# STlink_V3E_PWR.net
KiCad netlist of a schematic drawn in Altium Designer
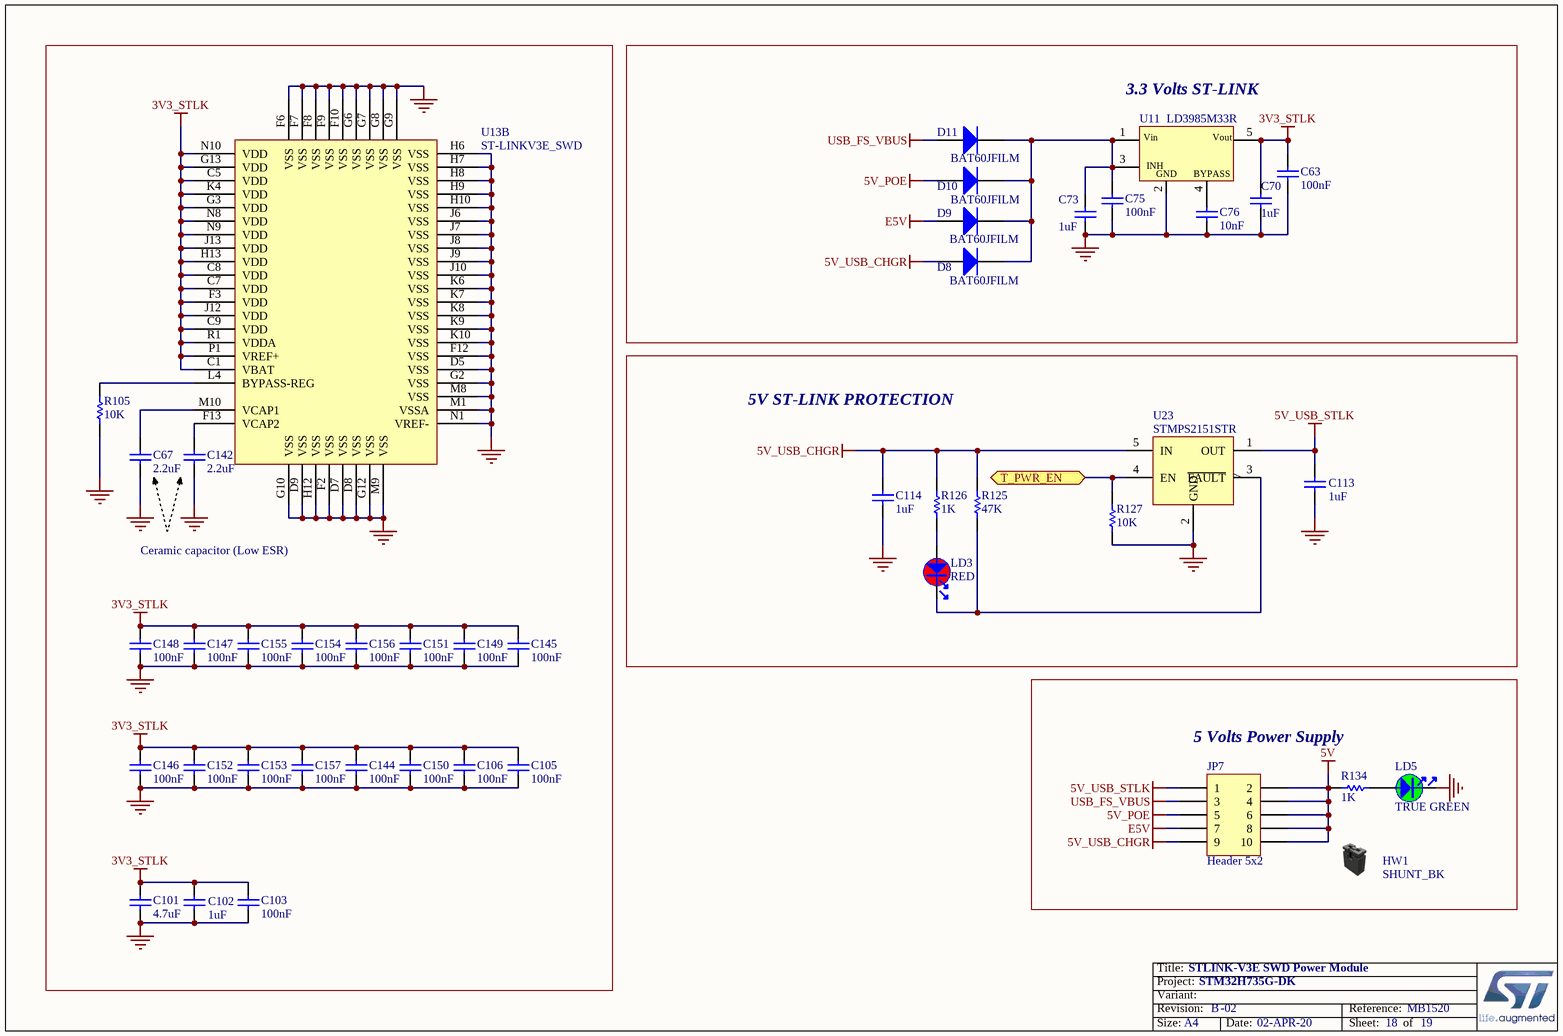
[diagram p0: STlink_V3E_PWR.SchDoc]

(export (version "E")
  (design (tool "Eeschema 10.0.6"))
  (components
    (comp (ref "C63")
      (value "100nF")
      (footprint "C0402")
      (description "Capacitor, MLCC, 100nF, 16V, X7R, 10%, 0402, T=0,5mm")
      (fields
        (field (name "INTERNAL_PART_NUMBER") "MCD-00102")
        (field (name "MANUFACTURER_PART_NUMBER") "CC0402KRX7R7BB104")
        (field (name "PROVIDED_BY") "SUBCO")
      )
      (libsource (lib "MCD_PARTS_database") (part "Capacitor"))
    )
    (comp (ref "C67")
      (value "2.2uF")
      (footprint "C1206_H1P15")
      (description "Capacitor, MLCC, 2.2uF, 16V, X7R, 10%, 1206, T=1,15mm")
      (fields
        (field (name "INTERNAL_PART_NUMBER") "MCD-00008")
        (field (name "MANUFACTURER_PART_NUMBER") "CC1206KKX7R7BB225")
        (field (name "PROVIDED_BY") "SUBCO")
      )
      (libsource (lib "MCD_PARTS_database") (part "Capacitor"))
    )
    (comp (ref "C70")
      (value "1uF")
      (footprint "C0603")
      (description "Capacitor, MLCC, 1uF, 16V, X5R, 10%, 0603, T=0,8mm")
      (fields
        (field (name "INTERNAL_PART_NUMBER") "MCD-00010")
        (field (name "MANUFACTURER_PART_NUMBER") "CC0603KRX5R7BB105")
        (field (name "PROVIDED_BY") "SUBCO")
      )
      (libsource (lib "MCD_PARTS_database") (part "Capacitor"))
    )
    (comp (ref "C73")
      (value "1uF")
      (footprint "C0603")
      (description "Capacitor, MLCC, 1uF, 6V3, X5R, 10%, 0603, T=0,8mm")
      (fields
        (field (name "INTERNAL_PART_NUMBER") "MCD-00238")
        (field (name "MANUFACTURER_PART_NUMBER") "CC0603KRX5R5BB105")
        (field (name "PROVIDED_BY") "SUBCO")
      )
      (libsource (lib "MCD_PARTS_database") (part "Capacitor"))
    )
    (comp (ref "C75")
      (value "100nF")
      (footprint "C0402")
      (description "Capacitor, MLCC, 100nF, 16V, X7R, 10%, 0402, T=0,5mm")
      (fields
        (field (name "INTERNAL_PART_NUMBER") "MCD-00102")
        (field (name "MANUFACTURER_PART_NUMBER") "CC0402KRX7R7BB104")
        (field (name "PROVIDED_BY") "SUBCO")
      )
      (libsource (lib "MCD_PARTS_database") (part "Capacitor"))
    )
    (comp (ref "C76")
      (value "10nF")
      (footprint "C0402")
      (description "Capacitor, MLCC, 10nF, 16V, X7R, 10%, 0402, T=0.5mm")
      (fields
        (field (name "INTERNAL_PART_NUMBER") "MCD-00011")
        (field (name "MANUFACTURER_PART_NUMBER") "CC0402KRX7R7BB103")
        (field (name "PROVIDED_BY") "SUBCO")
      )
      (libsource (lib "MCD_PARTS_database") (part "Capacitor"))
    )
    (comp (ref "C101")
      (value "4.7uF")
      (footprint "C0603")
      (description "Capacitor, MLCC, 4.7uF, 16V, X5R, 10%, 0603, T=0.8mm")
      (fields
        (field (name "INTERNAL_PART_NUMBER") "MCD-00009")
        (field (name "MANUFACTURER_PART_NUMBER") "CC0603KRX5R7BB475")
        (field (name "PROVIDED_BY") "SUBCO")
      )
      (libsource (lib "MCD_PARTS_database") (part "Capacitor"))
    )
    (comp (ref "C102")
      (value "1uF")
      (footprint "C0603")
      (description "Capacitor, MLCC, 1uF, 16V, X5R, 10%, 0603, T=0,8mm")
      (fields
        (field (name "INTERNAL_PART_NUMBER") "MCD-00010")
        (field (name "MANUFACTURER_PART_NUMBER") "CC0603KRX5R7BB105")
        (field (name "PROVIDED_BY") "SUBCO")
      )
      (libsource (lib "MCD_PARTS_database") (part "Capacitor"))
    )
    (comp (ref "C103")
      (value "100nF")
      (footprint "C0402")
      (description "Capacitor, MLCC, 100nF, 16V, X7R, 10%, 0402, T=0,5mm")
      (fields
        (field (name "INTERNAL_PART_NUMBER") "MCD-00102")
        (field (name "MANUFACTURER_PART_NUMBER") "CC0402KRX7R7BB104")
        (field (name "PROVIDED_BY") "SUBCO")
      )
      (libsource (lib "MCD_PARTS_database") (part "Capacitor"))
    )
    (comp (ref "C105")
      (value "100nF")
      (footprint "C0402")
      (description "Capacitor, MLCC, 100nF, 16V, X7R, 10%, 0402, T=0,5mm")
      (fields
        (field (name "INTERNAL_PART_NUMBER") "MCD-00102")
        (field (name "MANUFACTURER_PART_NUMBER") "CC0402KRX7R7BB104")
        (field (name "PROVIDED_BY") "SUBCO")
      )
      (libsource (lib "MCD_PARTS_database") (part "Capacitor"))
    )
    (comp (ref "C106")
      (value "100nF")
      (footprint "C0402")
      (description "Capacitor, MLCC, 100nF, 16V, X7R, 10%, 0402, T=0,5mm")
      (fields
        (field (name "INTERNAL_PART_NUMBER") "MCD-00102")
        (field (name "MANUFACTURER_PART_NUMBER") "CC0402KRX7R7BB104")
        (field (name "PROVIDED_BY") "SUBCO")
      )
      (libsource (lib "MCD_PARTS_database") (part "Capacitor"))
    )
    (comp (ref "C113")
      (value "1uF")
      (footprint "C0603")
      (description "Capacitor, MLCC, 1uF, 16V, X5R, 10%, 0603, T=0,8mm")
      (fields
        (field (name "INTERNAL_PART_NUMBER") "MCD-00010")
        (field (name "MANUFACTURER_PART_NUMBER") "CC0603KRX5R7BB105")
        (field (name "PROVIDED_BY") "SUBCO")
      )
      (libsource (lib "MCD_PARTS_database") (part "Capacitor"))
    )
    (comp (ref "C114")
      (value "1uF")
      (footprint "C0603")
      (description "Capacitor, MLCC, 1uF, 16V, X5R, 10%, 0603, T=0,8mm")
      (fields
        (field (name "INTERNAL_PART_NUMBER") "MCD-00010")
        (field (name "MANUFACTURER_PART_NUMBER") "CC0603KRX5R7BB105")
        (field (name "PROVIDED_BY") "SUBCO")
      )
      (libsource (lib "MCD_PARTS_database") (part "Capacitor"))
    )
    (comp (ref "C142")
      (value "2.2uF")
      (footprint "C1206_H1P15")
      (description "Capacitor, MLCC, 2.2uF, 16V, X7R, 10%, 1206, T=1,15mm")
      (fields
        (field (name "INTERNAL_PART_NUMBER") "MCD-00008")
        (field (name "MANUFACTURER_PART_NUMBER") "CC1206KKX7R7BB225")
        (field (name "PROVIDED_BY") "SUBCO")
      )
      (libsource (lib "MCD_PARTS_database") (part "Capacitor"))
    )
    (comp (ref "C144")
      (value "100nF")
      (footprint "C0402")
      (description "Capacitor, MLCC, 100nF, 16V, X7R, 10%, 0402, T=0,5mm")
      (fields
        (field (name "INTERNAL_PART_NUMBER") "MCD-00102")
        (field (name "MANUFACTURER_PART_NUMBER") "CC0402KRX7R7BB104")
        (field (name "PROVIDED_BY") "SUBCO")
      )
      (libsource (lib "MCD_PARTS_database") (part "Capacitor"))
    )
    (comp (ref "C145")
      (value "100nF")
      (footprint "C0402")
      (description "Capacitor, MLCC, 100nF, 16V, X7R, 10%, 0402, T=0,5mm")
      (fields
        (field (name "INTERNAL_PART_NUMBER") "MCD-00102")
        (field (name "MANUFACTURER_PART_NUMBER") "CC0402KRX7R7BB104")
        (field (name "PROVIDED_BY") "SUBCO")
      )
      (libsource (lib "MCD_PARTS_database") (part "Capacitor"))
    )
    (comp (ref "C146")
      (value "100nF")
      (footprint "C0402")
      (description "Capacitor, MLCC, 100nF, 16V, X7R, 10%, 0402, T=0,5mm")
      (fields
        (field (name "INTERNAL_PART_NUMBER") "MCD-00102")
        (field (name "MANUFACTURER_PART_NUMBER") "CC0402KRX7R7BB104")
        (field (name "PROVIDED_BY") "SUBCO")
      )
      (libsource (lib "MCD_PARTS_database") (part "Capacitor"))
    )
    (comp (ref "C147")
      (value "100nF")
      (footprint "C0402")
      (description "Capacitor, MLCC, 100nF, 16V, X7R, 10%, 0402, T=0,5mm")
      (fields
        (field (name "INTERNAL_PART_NUMBER") "MCD-00102")
        (field (name "MANUFACTURER_PART_NUMBER") "CC0402KRX7R7BB104")
        (field (name "PROVIDED_BY") "SUBCO")
      )
      (libsource (lib "MCD_PARTS_database") (part "Capacitor"))
    )
    (comp (ref "C148")
      (value "100nF")
      (footprint "C0402")
      (description "Capacitor, MLCC, 100nF, 16V, X7R, 10%, 0402, T=0,5mm")
      (fields
        (field (name "INTERNAL_PART_NUMBER") "MCD-00102")
        (field (name "MANUFACTURER_PART_NUMBER") "CC0402KRX7R7BB104")
        (field (name "PROVIDED_BY") "SUBCO")
      )
      (libsource (lib "MCD_PARTS_database") (part "Capacitor"))
    )
    (comp (ref "C149")
      (value "100nF")
      (footprint "C0402")
      (description "Capacitor, MLCC, 100nF, 16V, X7R, 10%, 0402, T=0,5mm")
      (fields
        (field (name "INTERNAL_PART_NUMBER") "MCD-00102")
        (field (name "MANUFACTURER_PART_NUMBER") "CC0402KRX7R7BB104")
        (field (name "PROVIDED_BY") "SUBCO")
      )
      (libsource (lib "MCD_PARTS_database") (part "Capacitor"))
    )
    (comp (ref "C150")
      (value "100nF")
      (footprint "C0402")
      (description "Capacitor, MLCC, 100nF, 16V, X7R, 10%, 0402, T=0,5mm")
      (fields
        (field (name "INTERNAL_PART_NUMBER") "MCD-00102")
        (field (name "MANUFACTURER_PART_NUMBER") "CC0402KRX7R7BB104")
        (field (name "PROVIDED_BY") "SUBCO")
      )
      (libsource (lib "MCD_PARTS_database") (part "Capacitor"))
    )
    (comp (ref "C151")
      (value "100nF")
      (footprint "C0402")
      (description "Capacitor, MLCC, 100nF, 16V, X7R, 10%, 0402, T=0,5mm")
      (fields
        (field (name "INTERNAL_PART_NUMBER") "MCD-00102")
        (field (name "MANUFACTURER_PART_NUMBER") "CC0402KRX7R7BB104")
        (field (name "PROVIDED_BY") "SUBCO")
      )
      (libsource (lib "MCD_PARTS_database") (part "Capacitor"))
    )
    (comp (ref "C152")
      (value "100nF")
      (footprint "C0402")
      (description "Capacitor, MLCC, 100nF, 16V, X7R, 10%, 0402, T=0,5mm")
      (fields
        (field (name "INTERNAL_PART_NUMBER") "MCD-00102")
        (field (name "MANUFACTURER_PART_NUMBER") "CC0402KRX7R7BB104")
        (field (name "PROVIDED_BY") "SUBCO")
      )
      (libsource (lib "MCD_PARTS_database") (part "Capacitor"))
    )
    (comp (ref "C153")
      (value "100nF")
      (footprint "C0402")
      (description "Capacitor, MLCC, 100nF, 16V, X7R, 10%, 0402, T=0,5mm")
      (fields
        (field (name "INTERNAL_PART_NUMBER") "MCD-00102")
        (field (name "MANUFACTURER_PART_NUMBER") "CC0402KRX7R7BB104")
        (field (name "PROVIDED_BY") "SUBCO")
      )
      (libsource (lib "MCD_PARTS_database") (part "Capacitor"))
    )
    (comp (ref "C154")
      (value "100nF")
      (footprint "C0402")
      (description "Capacitor, MLCC, 100nF, 16V, X7R, 10%, 0402, T=0,5mm")
      (fields
        (field (name "INTERNAL_PART_NUMBER") "MCD-00102")
        (field (name "MANUFACTURER_PART_NUMBER") "CC0402KRX7R7BB104")
        (field (name "PROVIDED_BY") "SUBCO")
      )
      (libsource (lib "MCD_PARTS_database") (part "Capacitor"))
    )
    (comp (ref "C155")
      (value "100nF")
      (footprint "C0402")
      (description "Capacitor, MLCC, 100nF, 16V, X7R, 10%, 0402, T=0,5mm")
      (fields
        (field (name "INTERNAL_PART_NUMBER") "MCD-00102")
        (field (name "MANUFACTURER_PART_NUMBER") "CC0402KRX7R7BB104")
        (field (name "PROVIDED_BY") "SUBCO")
      )
      (libsource (lib "MCD_PARTS_database") (part "Capacitor"))
    )
    (comp (ref "C156")
      (value "100nF")
      (footprint "C0402")
      (description "Capacitor, MLCC, 100nF, 16V, X7R, 10%, 0402, T=0,5mm")
      (fields
        (field (name "INTERNAL_PART_NUMBER") "MCD-00102")
        (field (name "MANUFACTURER_PART_NUMBER") "CC0402KRX7R7BB104")
        (field (name "PROVIDED_BY") "SUBCO")
      )
      (libsource (lib "MCD_PARTS_database") (part "Capacitor"))
    )
    (comp (ref "C157")
      (value "100nF")
      (footprint "C0402")
      (description "Capacitor, MLCC, 100nF, 16V, X7R, 10%, 0402, T=0,5mm")
      (fields
        (field (name "INTERNAL_PART_NUMBER") "MCD-00102")
        (field (name "MANUFACTURER_PART_NUMBER") "CC0402KRX7R7BB104")
        (field (name "PROVIDED_BY") "SUBCO")
      )
      (libsource (lib "MCD_PARTS_database") (part "Capacitor"))
    )
    (comp (ref "D8")
      (value "BAT60JFILM")
      (footprint "DIO_SOD323")
      (fields
        (field (name "INTERNAL_PART_NUMBER") "MCD-00034")
        (field (name "MANUFACTURER") "STMICROELECTRONICS")
        (field (name "BMS_PART_NUMBER") "9151097")
        (field (name "PROVIDED_BY") "SUBCO with ST control")
      )
      (libsource (lib "MCD_PARTS_database") (part "BAT60JFILM"))
    )
    (comp (ref "D9")
      (value "BAT60JFILM")
      (footprint "DIO_SOD323")
      (fields
        (field (name "INTERNAL_PART_NUMBER") "MCD-00034")
        (field (name "MANUFACTURER") "STMICROELECTRONICS")
        (field (name "BMS_PART_NUMBER") "9151097")
        (field (name "PROVIDED_BY") "SUBCO with ST control")
      )
      (libsource (lib "MCD_PARTS_database") (part "BAT60JFILM"))
    )
    (comp (ref "D10")
      (value "BAT60JFILM")
      (footprint "DIO_SOD323")
      (fields
        (field (name "INTERNAL_PART_NUMBER") "MCD-00034")
        (field (name "MANUFACTURER") "STMICROELECTRONICS")
        (field (name "BMS_PART_NUMBER") "9151097")
        (field (name "PROVIDED_BY") "SUBCO with ST control")
      )
      (libsource (lib "MCD_PARTS_database") (part "BAT60JFILM"))
    )
    (comp (ref "D11")
      (value "BAT60JFILM")
      (footprint "DIO_SOD323")
      (fields
        (field (name "INTERNAL_PART_NUMBER") "MCD-00034")
        (field (name "MANUFACTURER") "STMICROELECTRONICS")
        (field (name "BMS_PART_NUMBER") "9151097")
        (field (name "PROVIDED_BY") "SUBCO with ST control")
      )
      (libsource (lib "MCD_PARTS_database") (part "BAT60JFILM"))
    )
    (comp (ref "HW1")
      (value "SHUNT_BK")
      (footprint "NA")
      (description "SHUNT, 2.54mm, height 6.10mm, BLACK")
      (fields
        (field (name "INTERNAL_PART_NUMBER") "MCD-00122")
        (field (name "MANUFACTURER_PART_NUMBER") "SNT-100-BK-G")
        (field (name "PROVIDED_BY") "SUBCO")
      )
      (libsource (lib "MCD_PARTS_database") (part "Shunt Black 2.54mm"))
    )
    (comp (ref "JP7")
      (value "Header 5x2")
      (footprint "CON_988-JIUBABA_PHFS25-12-10-G0B115-T-1")
      (description "Header, 5x2, 2.54mm, VR, TH, Height 6mm/3mm")
      (fields
        (field (name "INTERNAL_PART_NUMBER") "MCD-00312")
        (field (name "MANUFACTURER_PART_NUMBER") "PHFS25-12-10-G0B115-T-1")
        (field (name "PROVIDED_BY") "SUBCO")
      )
      (libsource (lib "MCD_PARTS_database") (part "Header 5x2"))
    )
    (comp (ref "LD3")
      (value "RED")
      (footprint "LED_0603_VISHAY_VLMS1300-GS08_RED_1A2K_H0P8")
      (description "LED Red, 0603 SMD, 2V Forward Voltage")
      (fields
        (field (name "INTERNAL_PART_NUMBER") "MCD-00587")
        (field (name "MANUFACTURER_PART_NUMBER") "VLMS1300-GS08")
        (field (name "PROVIDED_BY") "SUBCO")
      )
      (libsource (lib "MCD_PARTS_database") (part "LED_red"))
    )
    (comp (ref "LD5")
      (value "TRUE GREEN")
      (footprint "LED_0603_VISHAY_VLMTG1300-GS08_GREEN_1A2K_H0P8")
      (description "LED Green, 0603 SMD, Fw Voltage = 2.8V - 3.6V")
      (fields
        (field (name "INTERNAL_PART_NUMBER") "MCD-00589")
        (field (name "MANUFACTURER_PART_NUMBER") "VLMTG1300-GS08")
        (field (name "PROVIDED_BY") "SUBCO")
      )
      (libsource (lib "MCD_PARTS_database") (part "LED_green"))
    )
    (comp (ref "R105")
      (value "10K")
      (footprint "R0402")
      (description "Resistor,10K,0402,1%,1/16W")
      (fields
        (field (name "INTERNAL_PART_NUMBER") "MCD-00053")
        (field (name "MANUFACTURER_PART_NUMBER") "RC0402FR-0710KL")
        (field (name "PROVIDED_BY") "SUBCO")
      )
      (libsource (lib "MCD_PARTS_database") (part "Resistor"))
    )
    (comp (ref "R125")
      (value "47K")
      (footprint "R0402")
      (description "Resistor,47K,0402,1%,1/16W")
      (fields
        (field (name "INTERNAL_PART_NUMBER") "MCD-00063")
        (field (name "MANUFACTURER_PART_NUMBER") "RC0402FR-0747KL")
        (field (name "PROVIDED_BY") "SUBCO")
      )
      (libsource (lib "MCD_PARTS_database") (part "Resistor"))
    )
    (comp (ref "R126")
      (value "1K")
      (footprint "R0402")
      (description "Resistor,1K,0402,1%,1/16W")
      (fields
        (field (name "INTERNAL_PART_NUMBER") "MCD-00061")
        (field (name "MANUFACTURER_PART_NUMBER") "RC0402FR-071KL")
        (field (name "PROVIDED_BY") "SUBCO")
      )
      (libsource (lib "MCD_PARTS_database") (part "Resistor"))
    )
    (comp (ref "R127")
      (value "10K")
      (footprint "R0402")
      (description "Resistor,10K,0402,1%,1/16W")
      (fields
        (field (name "INTERNAL_PART_NUMBER") "MCD-00053")
        (field (name "MANUFACTURER_PART_NUMBER") "RC0402FR-0710KL")
        (field (name "PROVIDED_BY") "SUBCO")
      )
      (libsource (lib "MCD_PARTS_database") (part "Resistor"))
    )
    (comp (ref "R134")
      (value "1K")
      (footprint "R0603")
      (description "Resistor,1K,0603,1%,1/10W")
      (fields
        (field (name "INTERNAL_PART_NUMBER") "MCD-00070")
        (field (name "MANUFACTURER_PART_NUMBER") "RC0603FR-071KL")
        (field (name "PROVIDED_BY") "SUBCO")
      )
      (libsource (lib "MCD_PARTS_database") (part "Resistor"))
    )
    (comp (ref "U11")
      (value "LD3985M33R")
      (footprint "REG_SOT23-5L")
      (description "Ultra low drop-low noise BiCMOS voltage, regulators low ESR capacitors compatible")
      (fields
        (field (name "INTERNAL_PART_NUMBER") "MCD-00086")
        (field (name "MANUFACTURER") "STMICROELECTRONICS")
        (field (name "PROVIDED_BY") "SUBCO with ST control")
      )
      (libsource (lib "MCD_PARTS_database") (part "LD3985M33R"))
    )
    (comp (ref "U13")
      (value "ST-LINKV3E_SWD")
      (footprint "ICC_UFBGA201_176+25_10X10_P065")
      (description "STM32F723IEK  (STM32F7) BGA176")
      (fields
        (field (name "INTERNAL_PART_NUMBER") "MCD-00596")
        (field (name "MANUFACTURER_PART_NUMBER") "STM32F723IEK6")
        (field (name "PROVIDED_BY") "SUBCO with ST control")
      )
      (libsource (lib "MCD_PARTS_database") (part "ST-LINKV3E_SWD"))
    )
    (comp (ref "U23")
      (value "STMPS2151STR")
      (footprint "MOS_SOT23-5L")
      (description "500mA, Enhanced single channel power switches with active high enable pin")
      (fields
        (field (name "INTERNAL_PART_NUMBER") "MCD-00159")
        (field (name "MANUFACTURER") "STMICROELECTRONICS")
        (field (name "PROVIDED_BY") "SUBCO with ST control")
      )
      (libsource (lib "MCD_PARTS_database") (part "STMPS2151STR"))
    )
  )
  (nets
    (net (code "1") (name "/T_PWR_EN") (class "Default")
      (node (ref "R127") (pin "1") (pinfunction "1_1") (pintype "passive"))
      (node (ref "U23") (pin "4") (pinfunction "EN_4") (pintype "passive"))
    )
    (net (code "2") (name "3V3_STLK") (class "Default")
      (node (ref "C101") (pin "2") (pinfunction "2_2") (pintype "passive"))
      (node (ref "C102") (pin "2") (pinfunction "2_2") (pintype "passive"))
      (node (ref "C103") (pin "2") (pinfunction "2_2") (pintype "passive"))
      (node (ref "C105") (pin "2") (pinfunction "2_2") (pintype "passive"))
      (node (ref "C106") (pin "2") (pinfunction "2_2") (pintype "passive"))
      (node (ref "C144") (pin "2") (pinfunction "2_2") (pintype "passive"))
      (node (ref "C145") (pin "2") (pinfunction "2_2") (pintype "passive"))
      (node (ref "C146") (pin "2") (pinfunction "2_2") (pintype "passive"))
      (node (ref "C147") (pin "2") (pinfunction "2_2") (pintype "passive"))
      (node (ref "C148") (pin "2") (pinfunction "2_2") (pintype "passive"))
      (node (ref "C149") (pin "2") (pinfunction "2_2") (pintype "passive"))
      (node (ref "C150") (pin "2") (pinfunction "2_2") (pintype "passive"))
      (node (ref "C151") (pin "2") (pinfunction "2_2") (pintype "passive"))
      (node (ref "C152") (pin "2") (pinfunction "2_2") (pintype "passive"))
      (node (ref "C153") (pin "2") (pinfunction "2_2") (pintype "passive"))
      (node (ref "C154") (pin "2") (pinfunction "2_2") (pintype "passive"))
      (node (ref "C155") (pin "2") (pinfunction "2_2") (pintype "passive"))
      (node (ref "C156") (pin "2") (pinfunction "2_2") (pintype "passive"))
      (node (ref "C157") (pin "2") (pinfunction "2_2") (pintype "passive"))
      (node (ref "C63") (pin "2") (pinfunction "2_2") (pintype "passive"))
      (node (ref "C70") (pin "2") (pinfunction "2_2") (pintype "passive"))
      (node (ref "U11") (pin "5") (pinfunction "Vout_5") (pintype "passive"))
      (node (ref "U13") (pin "C1") (pinfunction "VBAT_C1") (pintype "passive"))
      (node (ref "U13") (pin "C5") (pinfunction "VDD_C5") (pintype "passive"))
      (node (ref "U13") (pin "C7") (pinfunction "VDD_C7") (pintype "passive"))
      (node (ref "U13") (pin "C8") (pinfunction "VDD_C8") (pintype "passive"))
      (node (ref "U13") (pin "C9") (pinfunction "VDD_C9") (pintype "passive"))
      (node (ref "U13") (pin "F3") (pinfunction "VDD_F3") (pintype "passive"))
      (node (ref "U13") (pin "G13") (pinfunction "VDD_G13") (pintype "passive"))
      (node (ref "U13") (pin "G3") (pinfunction "VDD_G3") (pintype "passive"))
      (node (ref "U13") (pin "H13") (pinfunction "VDD_H13") (pintype "passive"))
      (node (ref "U13") (pin "J12") (pinfunction "VDD_J12") (pintype "passive"))
      (node (ref "U13") (pin "J13") (pinfunction "VDD_J13") (pintype "passive"))
      (node (ref "U13") (pin "K4") (pinfunction "VDD_K4") (pintype "passive"))
      (node (ref "U13") (pin "N10") (pinfunction "VDD_N10") (pintype "passive"))
      (node (ref "U13") (pin "N8") (pinfunction "VDD_N8") (pintype "passive"))
      (node (ref "U13") (pin "N9") (pinfunction "VDD_N9") (pintype "passive"))
      (node (ref "U13") (pin "P1") (pinfunction "VREF+_P1") (pintype "passive"))
      (node (ref "U13") (pin "R1") (pinfunction "VDDA_R1") (pintype "passive"))
    )
    (net (code "3") (name "5V") (class "Default")
      (node (ref "JP7") (pin "10") (pinfunction "10_10") (pintype "passive"))
      (node (ref "JP7") (pin "2") (pinfunction "2_2") (pintype "passive"))
      (node (ref "JP7") (pin "4") (pinfunction "4_4") (pintype "passive"))
      (node (ref "JP7") (pin "6") (pinfunction "6_6") (pintype "passive"))
      (node (ref "JP7") (pin "8") (pinfunction "8_8") (pintype "passive"))
      (node (ref "R134") (pin "1") (pinfunction "1_1") (pintype "passive"))
    )
    (net (code "4") (name "5V_POE") (class "Default")
      (node (ref "D10") (pin "1") (pinfunction "A_1") (pintype "passive"))
      (node (ref "JP7") (pin "5") (pinfunction "5_5") (pintype "passive"))
    )
    (net (code "5") (name "5V_USB_CHGR") (class "Default")
      (node (ref "C114") (pin "2") (pinfunction "2_2") (pintype "passive"))
      (node (ref "D8") (pin "1") (pinfunction "A_1") (pintype "passive"))
      (node (ref "JP7") (pin "9") (pinfunction "9_9") (pintype "passive"))
      (node (ref "R125") (pin "2") (pinfunction "2_2") (pintype "passive"))
      (node (ref "R126") (pin "2") (pinfunction "2_2") (pintype "passive"))
      (node (ref "U23") (pin "5") (pinfunction "IN_5") (pintype "passive"))
    )
    (net (code "6") (name "5V_USB_STLK") (class "Default")
      (node (ref "C113") (pin "2") (pinfunction "2_2") (pintype "passive"))
      (node (ref "JP7") (pin "1") (pinfunction "1_1") (pintype "passive"))
      (node (ref "U23") (pin "1") (pinfunction "OUT_1") (pintype "passive"))
    )
    (net (code "7") (name "E5V") (class "Default")
      (node (ref "D9") (pin "1") (pinfunction "A_1") (pintype "passive"))
      (node (ref "JP7") (pin "7") (pinfunction "7_7") (pintype "passive"))
    )
    (net (code "8") (name "GND") (class "Default")
      (node (ref "C101") (pin "1") (pinfunction "1_1") (pintype "passive"))
      (node (ref "C102") (pin "1") (pinfunction "1_1") (pintype "passive"))
      (node (ref "C103") (pin "1") (pinfunction "1_1") (pintype "passive"))
      (node (ref "C105") (pin "1") (pinfunction "1_1") (pintype "passive"))
      (node (ref "C106") (pin "1") (pinfunction "1_1") (pintype "passive"))
      (node (ref "C113") (pin "1") (pinfunction "1_1") (pintype "passive"))
      (node (ref "C114") (pin "1") (pinfunction "1_1") (pintype "passive"))
      (node (ref "C142") (pin "1") (pinfunction "1_1") (pintype "passive"))
      (node (ref "C144") (pin "1") (pinfunction "1_1") (pintype "passive"))
      (node (ref "C145") (pin "1") (pinfunction "1_1") (pintype "passive"))
      (node (ref "C146") (pin "1") (pinfunction "1_1") (pintype "passive"))
      (node (ref "C147") (pin "1") (pinfunction "1_1") (pintype "passive"))
      (node (ref "C148") (pin "1") (pinfunction "1_1") (pintype "passive"))
      (node (ref "C149") (pin "1") (pinfunction "1_1") (pintype "passive"))
      (node (ref "C150") (pin "1") (pinfunction "1_1") (pintype "passive"))
      (node (ref "C151") (pin "1") (pinfunction "1_1") (pintype "passive"))
      (node (ref "C152") (pin "1") (pinfunction "1_1") (pintype "passive"))
      (node (ref "C153") (pin "1") (pinfunction "1_1") (pintype "passive"))
      (node (ref "C154") (pin "1") (pinfunction "1_1") (pintype "passive"))
      (node (ref "C155") (pin "1") (pinfunction "1_1") (pintype "passive"))
      (node (ref "C156") (pin "1") (pinfunction "1_1") (pintype "passive"))
      (node (ref "C157") (pin "1") (pinfunction "1_1") (pintype "passive"))
      (node (ref "C63") (pin "1") (pinfunction "1_1") (pintype "passive"))
      (node (ref "C67") (pin "1") (pinfunction "1_1") (pintype "passive"))
      (node (ref "C70") (pin "1") (pinfunction "1_1") (pintype "passive"))
      (node (ref "C73") (pin "2") (pinfunction "2_2") (pintype "passive"))
      (node (ref "C75") (pin "1") (pinfunction "1_1") (pintype "passive"))
      (node (ref "C76") (pin "1") (pinfunction "1_1") (pintype "passive"))
      (node (ref "LD5") (pin "2") (pintype "passive"))
      (node (ref "R105") (pin "1") (pinfunction "1_1") (pintype "passive"))
      (node (ref "R127") (pin "2") (pinfunction "2_2") (pintype "passive"))
      (node (ref "U11") (pin "2") (pinfunction "GND_2") (pintype "passive"))
      (node (ref "U13") (pin "D5") (pinfunction "VSS_D5") (pintype "passive"))
      (node (ref "U13") (pin "D7") (pinfunction "VSS_D7") (pintype "passive"))
      (node (ref "U13") (pin "D8") (pinfunction "VSS_D8") (pintype "passive"))
      (node (ref "U13") (pin "D9") (pinfunction "VSS_D9") (pintype "passive"))
      (node (ref "U13") (pin "F10") (pinfunction "VSS_F10") (pintype "passive"))
      (node (ref "U13") (pin "F12") (pinfunction "VSS_F12") (pintype "passive"))
      (node (ref "U13") (pin "F2") (pinfunction "VSS_F2") (pintype "passive"))
      (node (ref "U13") (pin "F6") (pinfunction "VSS_F6") (pintype "passive"))
      (node (ref "U13") (pin "F7") (pinfunction "VSS_F7") (pintype "passive"))
      (node (ref "U13") (pin "F8") (pinfunction "VSS_F8") (pintype "passive"))
      (node (ref "U13") (pin "F9") (pinfunction "VSS_F9") (pintype "passive"))
      (node (ref "U13") (pin "G10") (pinfunction "VSS_G10") (pintype "passive"))
      (node (ref "U13") (pin "G12") (pinfunction "VSS_G12") (pintype "passive"))
      (node (ref "U13") (pin "G2") (pinfunction "VSS_G2") (pintype "passive"))
      (node (ref "U13") (pin "G6") (pinfunction "VSS_G6") (pintype "passive"))
      (node (ref "U13") (pin "G7") (pinfunction "VSS_G7") (pintype "passive"))
      (node (ref "U13") (pin "G8") (pinfunction "VSS_G8") (pintype "passive"))
      (node (ref "U13") (pin "G9") (pinfunction "VSS_G9") (pintype "passive"))
      (node (ref "U13") (pin "H10") (pinfunction "VSS_H10") (pintype "passive"))
      (node (ref "U13") (pin "H12") (pinfunction "VSS_H12") (pintype "passive"))
      (node (ref "U13") (pin "H6") (pinfunction "VSS_H6") (pintype "passive"))
      (node (ref "U13") (pin "H7") (pinfunction "VSS_H7") (pintype "passive"))
      (node (ref "U13") (pin "H8") (pinfunction "VSS_H8") (pintype "passive"))
      (node (ref "U13") (pin "H9") (pinfunction "VSS_H9") (pintype "passive"))
      (node (ref "U13") (pin "J10") (pinfunction "VSS_J10") (pintype "passive"))
      (node (ref "U13") (pin "J6") (pinfunction "VSS_J6") (pintype "passive"))
      (node (ref "U13") (pin "J7") (pinfunction "VSS_J7") (pintype "passive"))
      (node (ref "U13") (pin "J8") (pinfunction "VSS_J8") (pintype "passive"))
      (node (ref "U13") (pin "J9") (pinfunction "VSS_J9") (pintype "passive"))
      (node (ref "U13") (pin "K10") (pinfunction "VSS_K10") (pintype "passive"))
      (node (ref "U13") (pin "K6") (pinfunction "VSS_K6") (pintype "passive"))
      (node (ref "U13") (pin "K7") (pinfunction "VSS_K7") (pintype "passive"))
      (node (ref "U13") (pin "K8") (pinfunction "VSS_K8") (pintype "passive"))
      (node (ref "U13") (pin "K9") (pinfunction "VSS_K9") (pintype "passive"))
      (node (ref "U13") (pin "M1") (pinfunction "VSSA_M1") (pintype "passive"))
      (node (ref "U13") (pin "M8") (pinfunction "VSS_M8") (pintype "passive"))
      (node (ref "U13") (pin "M9") (pinfunction "VSS_M9") (pintype "passive"))
      (node (ref "U13") (pin "N1") (pinfunction "VREF-_N1") (pintype "passive"))
      (node (ref "U23") (pin "2") (pinfunction "GND_2") (pintype "passive"))
    )
    (net (code "9") (name "Net-(D10-K)") (class "Default")
      (node (ref "C73") (pin "1") (pinfunction "1_1") (pintype "passive"))
      (node (ref "C75") (pin "2") (pinfunction "2_2") (pintype "passive"))
      (node (ref "D10") (pin "2") (pinfunction "K_2") (pintype "passive"))
      (node (ref "D11") (pin "2") (pinfunction "K_2") (pintype "passive"))
      (node (ref "D8") (pin "2") (pinfunction "K_2") (pintype "passive"))
      (node (ref "D9") (pin "2") (pinfunction "K_2") (pintype "passive"))
      (node (ref "U11") (pin "1") (pinfunction "Vin_1") (pintype "passive"))
      (node (ref "U11") (pin "3") (pinfunction "CE_3") (pintype "passive"))
    )
    (net (code "10") (name "Net-(LD3-Pad1)") (class "Default")
      (node (ref "LD3") (pin "1") (pintype "passive"))
      (node (ref "R126") (pin "1") (pinfunction "1_1") (pintype "passive"))
    )
    (net (code "11") (name "Net-(LD5-Pad1)") (class "Default")
      (node (ref "LD5") (pin "1") (pintype "passive"))
      (node (ref "R134") (pin "2") (pinfunction "2_2") (pintype "passive"))
    )
    (net (code "12") (name "Net-(U11-BYPASS)") (class "Default")
      (node (ref "C76") (pin "2") (pinfunction "2_2") (pintype "passive"))
      (node (ref "U11") (pin "4") (pinfunction "BYPASS_4") (pintype "passive"))
    )
    (net (code "13") (name "Net-(U13B-BYPASS-REG)") (class "Default")
      (node (ref "R105") (pin "2") (pinfunction "2_2") (pintype "passive"))
      (node (ref "U13") (pin "L4") (pinfunction "BYPASS-REG_L4") (pintype "passive"))
    )
    (net (code "14") (name "Net-(U13B-VCAP1)") (class "Default")
      (node (ref "C67") (pin "2") (pinfunction "2_2") (pintype "passive"))
      (node (ref "U13") (pin "M10") (pinfunction "VCAP1_M10") (pintype "passive"))
    )
    (net (code "15") (name "Net-(U13B-VCAP2)") (class "Default")
      (node (ref "C142") (pin "2") (pinfunction "2_2") (pintype "passive"))
      (node (ref "U13") (pin "F13") (pinfunction "VCAP2_F13") (pintype "passive"))
    )
    (net (code "16") (name "Net-(U23-~{FAULT})") (class "Default")
      (node (ref "LD3") (pin "2") (pintype "passive"))
      (node (ref "R125") (pin "1") (pinfunction "1_1") (pintype "passive"))
      (node (ref "U23") (pin "3") (pinfunction "~{FAULT}_3") (pintype "passive"))
    )
    (net (code "17") (name "USB_FS_VBUS") (class "Default")
      (node (ref "D11") (pin "1") (pinfunction "A_1") (pintype "passive"))
      (node (ref "JP7") (pin "3") (pinfunction "3_3") (pintype "passive"))
    )
  )
)
